# MCB-Wise-1530-v2_0_0.net
KiCad netlist of a schematic drawn in EAGLE
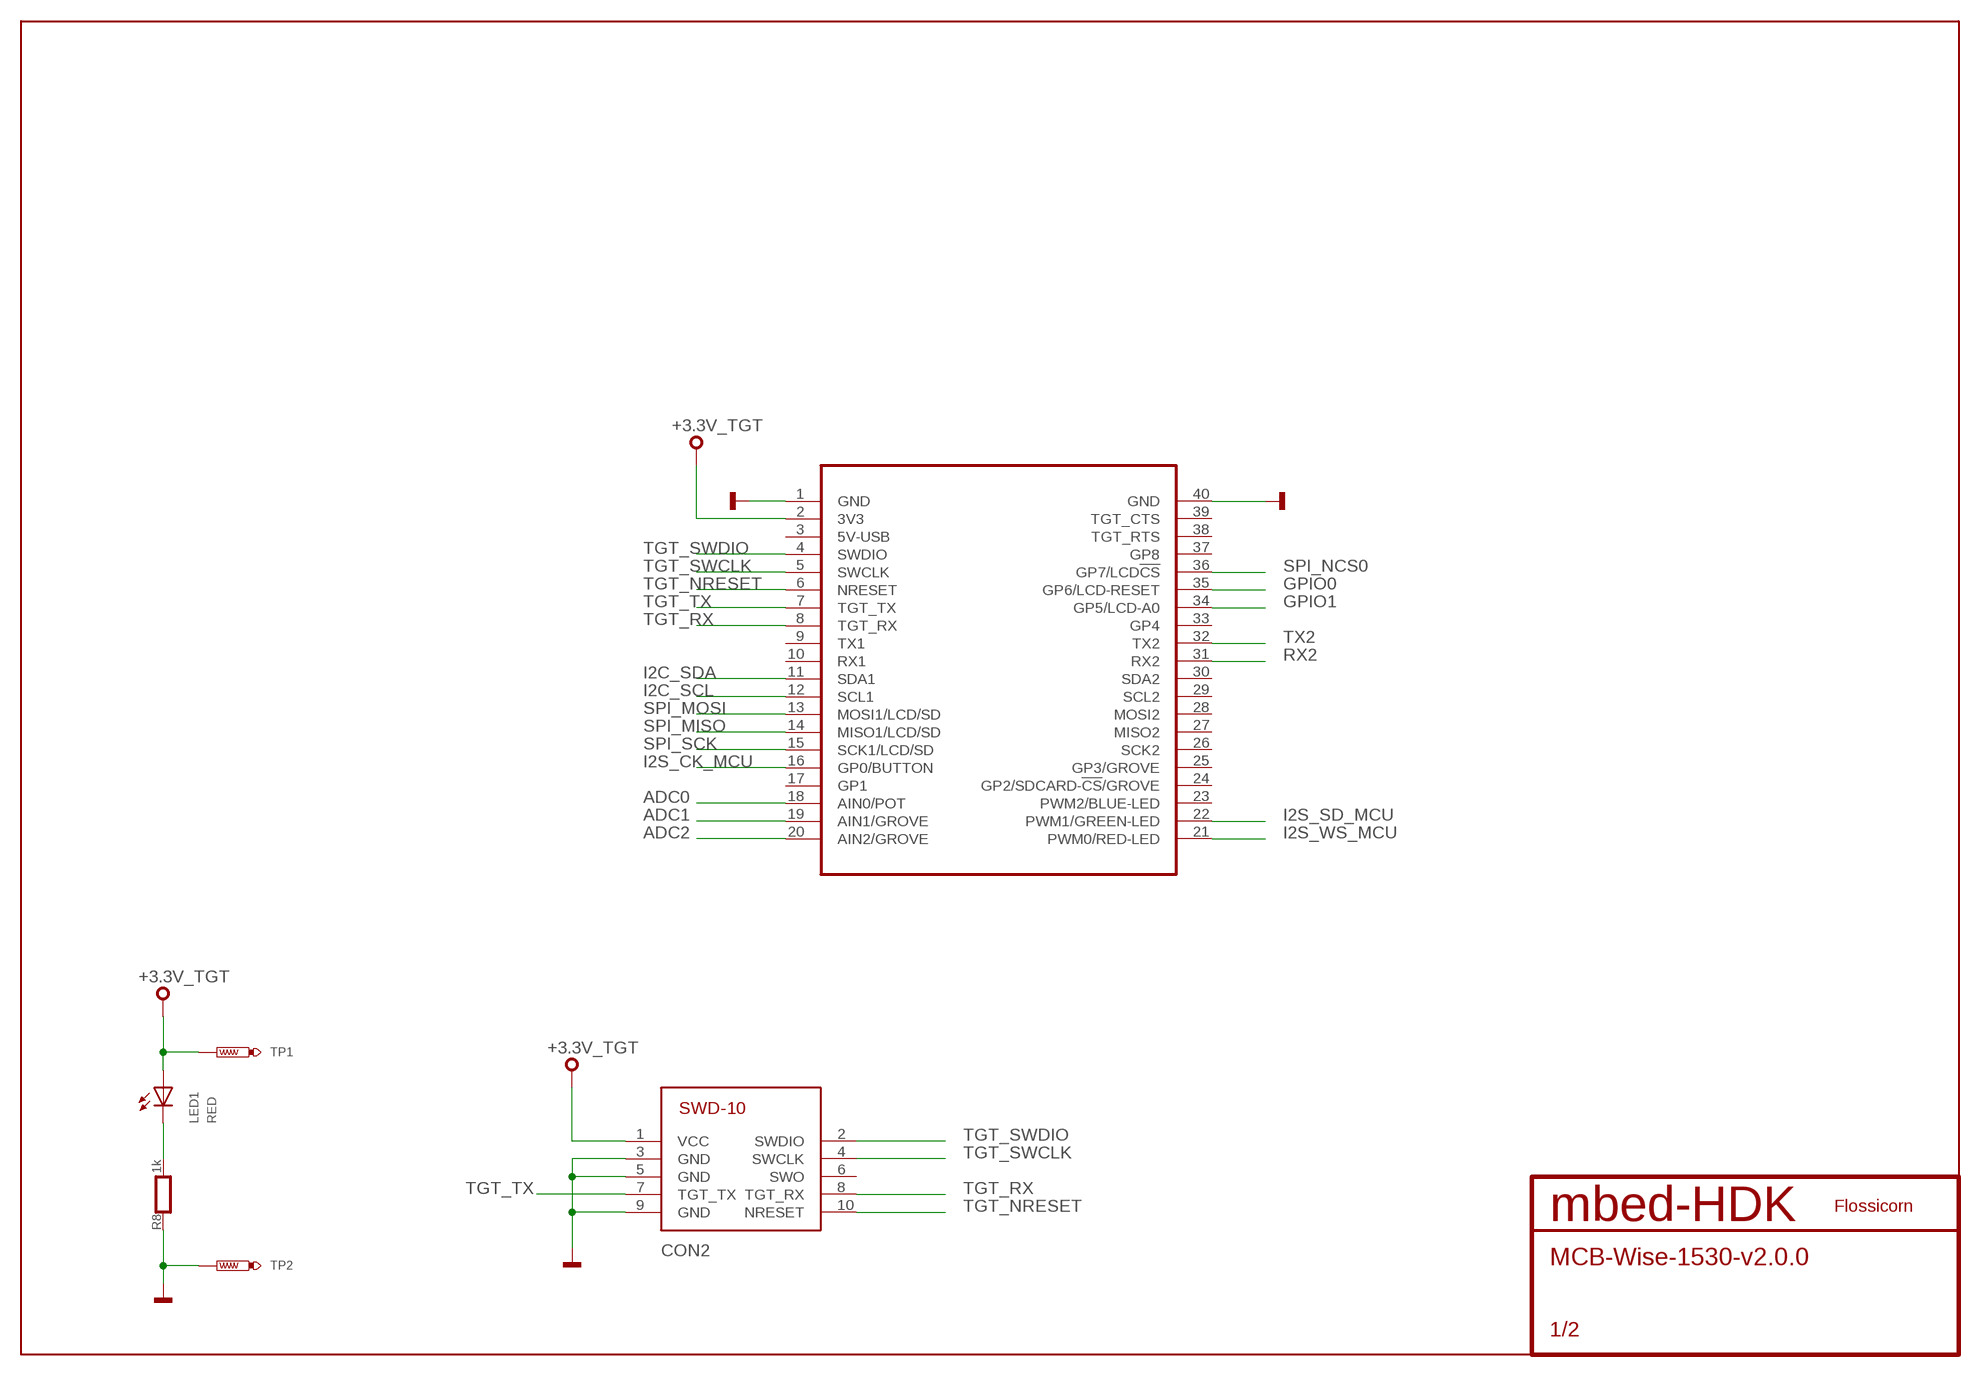
[diagram p0: schematic, sheet 1]
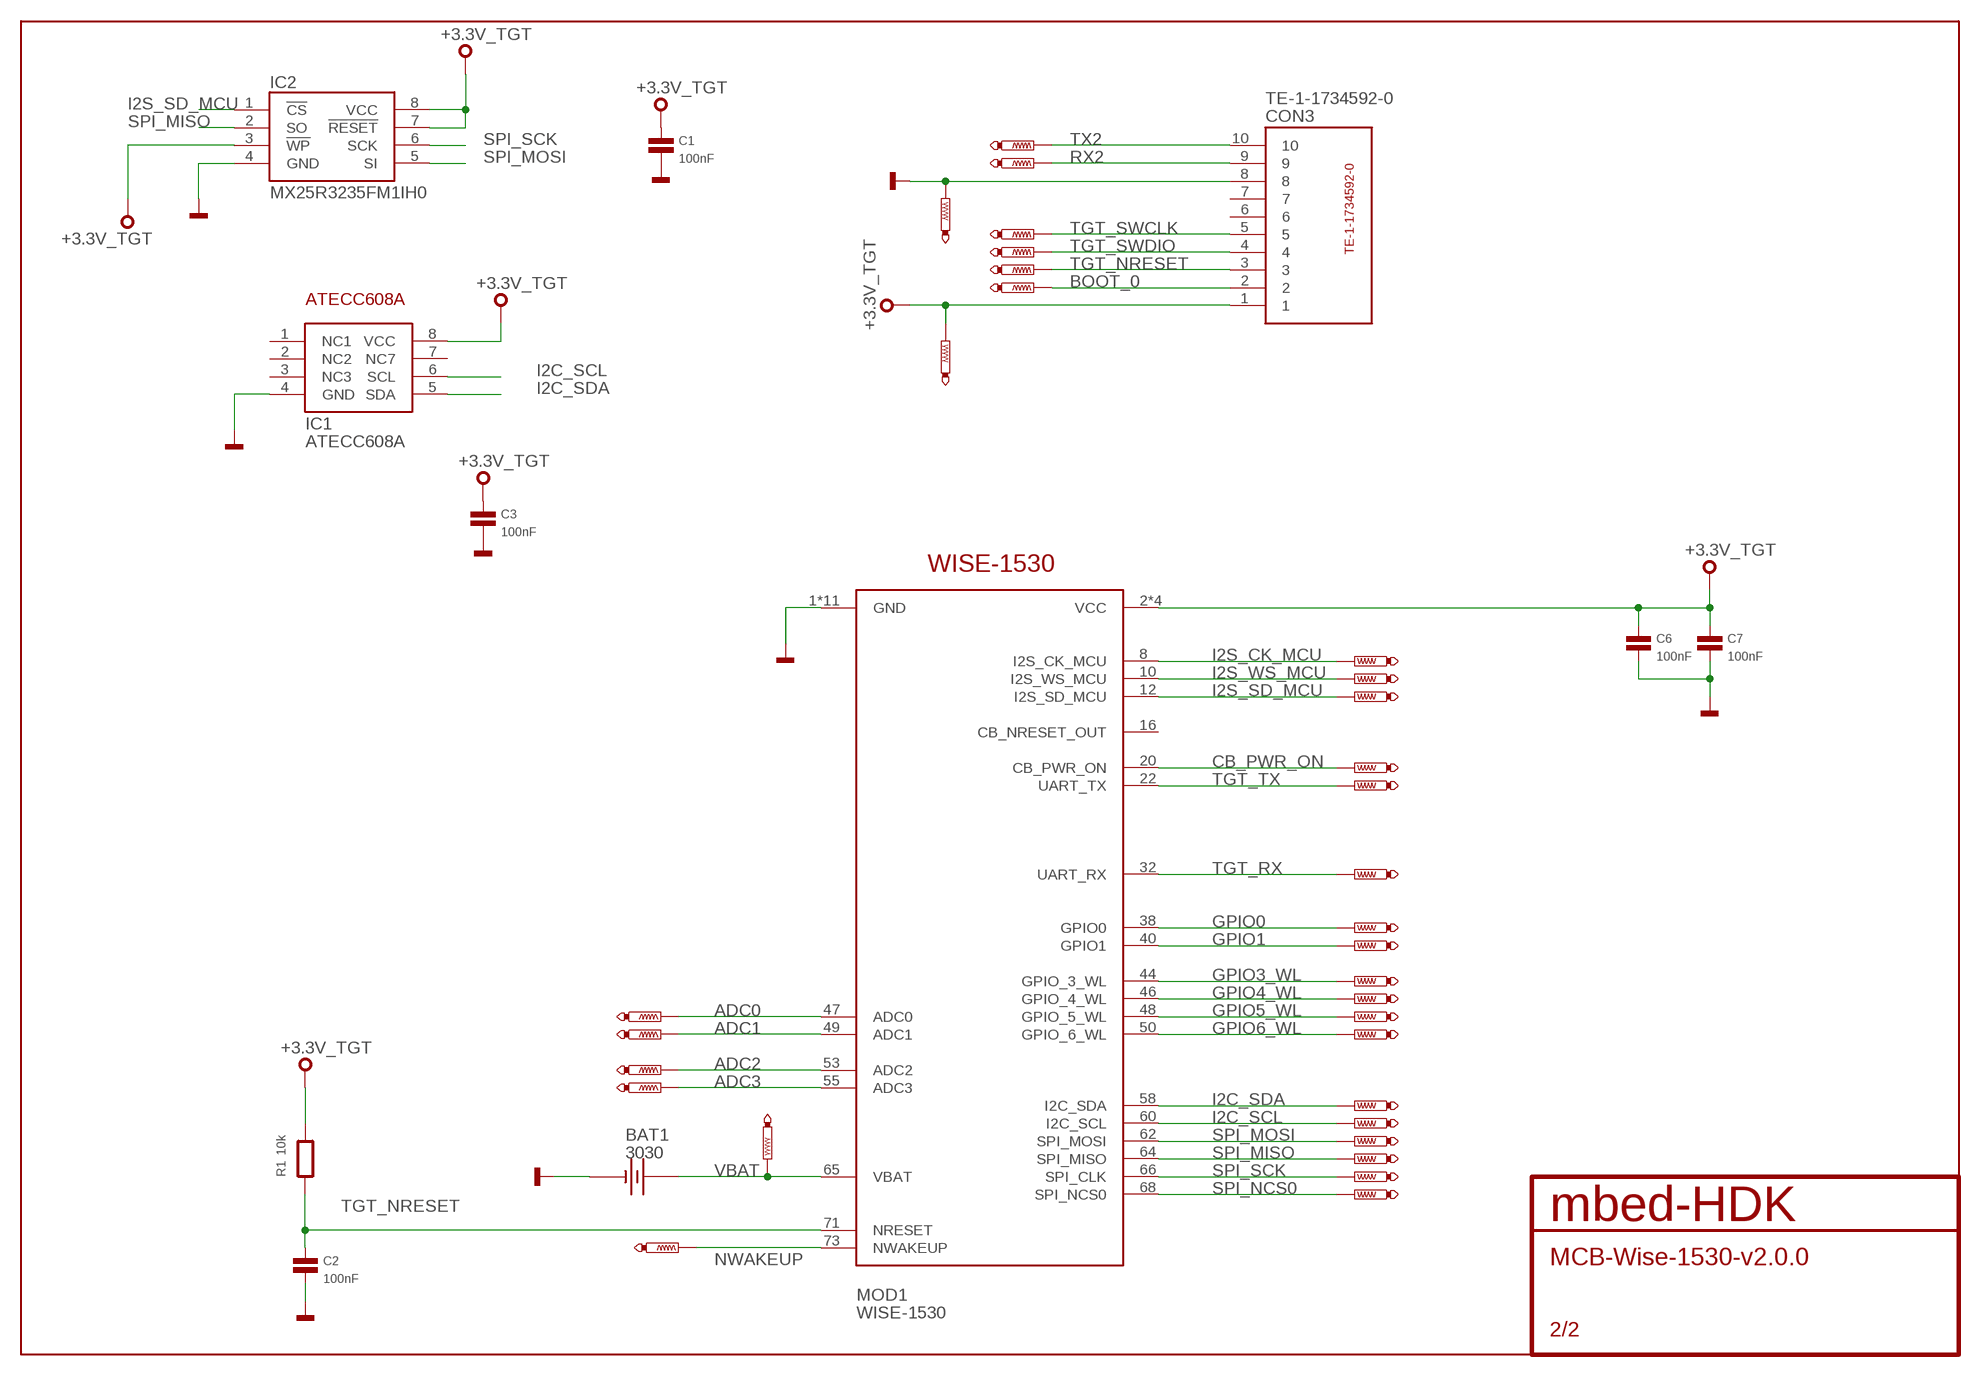
[diagram p1: schematic, sheet 2]

(export (version "E")
  (design (tool "Eeschema 10.0.6"))
  (components
    (comp (ref "CON2")
      (value "SWD-10/TC2050_SMD")
      (footprint "eagle-import:FTSH-105-02")
      (libsource (lib "eagle-import") (part "SWD-10/TC2050_SMD"))
    )
    (comp (ref "LED1")
      (value "RED")
      (footprint "eagle-import:CHIPLED_0603")
      (fields (field (name "MF") "Wurth Electronics Inc"))
      (libsource (lib "eagle-import") (part "SMD_LED0603"))
    )
    (comp (ref "MOD2")
      (value "MODULE_DAUGHTER")
      (footprint "eagle-import:MODULE_DAUGHTER")
      (libsource (lib "eagle-import") (part "MODULE_DAUGHTER"))
    )
    (comp (ref "R8")
      (value "1k")
      (footprint "eagle-import:0603")
      (libsource (lib "eagle-import") (part "RESISTOR0603"))
    )
    (comp (ref "SS1")
      (value "FLOSSICORN0.25")
      (footprint "eagle-import:FLOSSICORN-0.25")
      (libsource (lib "eagle-import") (part "FLOSSICORN0.25"))
    )
    (comp (ref "TP1")
      (value "TEST-POINT-50R-PTH")
      (footprint "eagle-import:TP50-PTH")
      (libsource (lib "eagle-import") (part "TEST-POINT-50R-PTH"))
    )
    (comp (ref "TP2")
      (value "TEST-POINT-50R-PTH")
      (footprint "eagle-import:TP50-PTH")
      (libsource (lib "eagle-import") (part "TEST-POINT-50R-PTH"))
    )
    (comp (ref "BAT1")
      (value "3030")
      (footprint "eagle-import:3030")
      (fields (field (name "MF") "Keystone"))
      (libsource (lib "eagle-import") (part "3030"))
    )
    (comp (ref "C1")
      (value "100nF")
      (footprint "eagle-import:0603")
      (libsource (lib "eagle-import") (part "CAPACITOR0603"))
    )
    (comp (ref "C2")
      (value "100nF")
      (footprint "eagle-import:0603")
      (libsource (lib "eagle-import") (part "CAPACITOR0603"))
    )
    (comp (ref "C3")
      (value "100nF")
      (footprint "eagle-import:0603")
      (libsource (lib "eagle-import") (part "CAPACITOR0603"))
    )
    (comp (ref "C6")
      (value "100nF")
      (footprint "eagle-import:0603")
      (libsource (lib "eagle-import") (part "CAPACITOR0603"))
    )
    (comp (ref "C7")
      (value "100nF")
      (footprint "eagle-import:0603")
      (libsource (lib "eagle-import") (part "CAPACITOR0603"))
    )
    (comp (ref "CON3")
      (value "TE-1-1734592-0")
      (footprint "eagle-import:TE-1-1734592-0")
      (libsource (lib "eagle-import") (part "TE-1-1734592-0"))
    )
    (comp (ref "IC1")
      (value "ATECC608A")
      (footprint "eagle-import:SO8")
      (libsource (lib "eagle-import") (part "ATECC608A"))
    )
    (comp (ref "IC2")
      (value "MX25R3235FM1IH0")
      (footprint "eagle-import:SO8")
      (fields (field (name "MF") "Macronix"))
      (libsource (lib "eagle-import") (part "MX25R3235FM1IH0"))
    )
    (comp (ref "MOD1")
      (value "WISE-1530")
      (footprint "eagle-import:MDT420E02001")
      (libsource (lib "eagle-import") (part "WISE-1530"))
    )
    (comp (ref "R1")
      (value "10k")
      (footprint "eagle-import:0603")
      (libsource (lib "eagle-import") (part "RESISTOR0603"))
    )
    (comp (ref "TP3")
      (value "PTR1TP08R")
      (footprint "eagle-import:TP08R")
      (libsource (lib "eagle-import") (part "PTR1TP08R"))
    )
    (comp (ref "TP4")
      (value "PTR1TP08R")
      (footprint "eagle-import:TP08R")
      (libsource (lib "eagle-import") (part "PTR1TP08R"))
    )
    (comp (ref "TP5")
      (value "PTR1TP08R")
      (footprint "eagle-import:TP08R")
      (libsource (lib "eagle-import") (part "PTR1TP08R"))
    )
    (comp (ref "TP6")
      (value "PTR1TP08R")
      (footprint "eagle-import:TP08R")
      (libsource (lib "eagle-import") (part "PTR1TP08R"))
    )
    (comp (ref "TP7")
      (value "PTR1TP08R")
      (footprint "eagle-import:TP08R")
      (libsource (lib "eagle-import") (part "PTR1TP08R"))
    )
    (comp (ref "TP8")
      (value "PTR1TP08R")
      (footprint "eagle-import:TP08R")
      (libsource (lib "eagle-import") (part "PTR1TP08R"))
    )
    (comp (ref "TP9")
      (value "PTR1TP07R")
      (footprint "eagle-import:TP07R")
      (libsource (lib "eagle-import") (part "PTR1TP07R"))
    )
    (comp (ref "TP10")
      (value "PTR1TP07R")
      (footprint "eagle-import:TP07R")
      (libsource (lib "eagle-import") (part "PTR1TP07R"))
    )
    (comp (ref "TP11")
      (value "PTR1TP07R")
      (footprint "eagle-import:TP07R")
      (libsource (lib "eagle-import") (part "PTR1TP07R"))
    )
    (comp (ref "TP12")
      (value "PTR1TP08R")
      (footprint "eagle-import:TP08R")
      (libsource (lib "eagle-import") (part "PTR1TP08R"))
    )
    (comp (ref "TP13")
      (value "PTR1TP08R")
      (footprint "eagle-import:TP08R")
      (libsource (lib "eagle-import") (part "PTR1TP08R"))
    )
    (comp (ref "TP14")
      (value "PTR1TP07R")
      (footprint "eagle-import:TP07R")
      (libsource (lib "eagle-import") (part "PTR1TP07R"))
    )
    (comp (ref "TP15")
      (value "PTR1TP07R")
      (footprint "eagle-import:TP07R")
      (libsource (lib "eagle-import") (part "PTR1TP07R"))
    )
    (comp (ref "TP16")
      (value "PTR1TP07R")
      (footprint "eagle-import:TP07R")
      (libsource (lib "eagle-import") (part "PTR1TP07R"))
    )
    (comp (ref "TP17")
      (value "PTR1TP07R")
      (footprint "eagle-import:TP07R")
      (libsource (lib "eagle-import") (part "PTR1TP07R"))
    )
    (comp (ref "TP18")
      (value "PTR1TP07R")
      (footprint "eagle-import:TP07R")
      (libsource (lib "eagle-import") (part "PTR1TP07R"))
    )
    (comp (ref "TP19")
      (value "PTR1TP07R")
      (footprint "eagle-import:TP07R")
      (libsource (lib "eagle-import") (part "PTR1TP07R"))
    )
    (comp (ref "TP20")
      (value "PTR1TP07R")
      (footprint "eagle-import:TP07R")
      (libsource (lib "eagle-import") (part "PTR1TP07R"))
    )
    (comp (ref "TP21")
      (value "PTR1TP07R")
      (footprint "eagle-import:TP07R")
      (libsource (lib "eagle-import") (part "PTR1TP07R"))
    )
    (comp (ref "TP22")
      (value "PTR1TP07R")
      (footprint "eagle-import:TP07R")
      (libsource (lib "eagle-import") (part "PTR1TP07R"))
    )
    (comp (ref "TP23")
      (value "PTR1TP07R")
      (footprint "eagle-import:TP07R")
      (libsource (lib "eagle-import") (part "PTR1TP07R"))
    )
    (comp (ref "TP24")
      (value "PTR1TP07R")
      (footprint "eagle-import:TP07R")
      (libsource (lib "eagle-import") (part "PTR1TP07R"))
    )
    (comp (ref "TP25")
      (value "PTR1TP07R")
      (footprint "eagle-import:TP07R")
      (libsource (lib "eagle-import") (part "PTR1TP07R"))
    )
    (comp (ref "TP26")
      (value "PTR1TP07R")
      (footprint "eagle-import:TP07R")
      (libsource (lib "eagle-import") (part "PTR1TP07R"))
    )
    (comp (ref "TP27")
      (value "PTR1TP07R")
      (footprint "eagle-import:TP07R")
      (libsource (lib "eagle-import") (part "PTR1TP07R"))
    )
    (comp (ref "TP28")
      (value "PTR1TP07R")
      (footprint "eagle-import:TP07R")
      (libsource (lib "eagle-import") (part "PTR1TP07R"))
    )
    (comp (ref "TP29")
      (value "PTR1TP07R")
      (footprint "eagle-import:TP07R")
      (libsource (lib "eagle-import") (part "PTR1TP07R"))
    )
    (comp (ref "TP30")
      (value "PTR1TP07R")
      (footprint "eagle-import:TP07R")
      (libsource (lib "eagle-import") (part "PTR1TP07R"))
    )
    (comp (ref "TP31")
      (value "PTR1TP07R")
      (footprint "eagle-import:TP07R")
      (libsource (lib "eagle-import") (part "PTR1TP07R"))
    )
    (comp (ref "TP32")
      (value "PTR1TP07R")
      (footprint "eagle-import:TP07R")
      (libsource (lib "eagle-import") (part "PTR1TP07R"))
    )
    (comp (ref "TP33")
      (value "PTR1TP07R")
      (footprint "eagle-import:TP07R")
      (libsource (lib "eagle-import") (part "PTR1TP07R"))
    )
    (comp (ref "TP34")
      (value "PTR1TP07R")
      (footprint "eagle-import:TP07R")
      (libsource (lib "eagle-import") (part "PTR1TP07R"))
    )
  )
  (nets
    (net (code "1") (name "+3.3V_TGT") (class "Default")
      (node (ref "C1") (pin "1") (pinfunction "P$1_1") (pintype "passive"))
      (node (ref "C3") (pin "1") (pinfunction "P$1_1") (pintype "passive"))
      (node (ref "C6") (pin "1") (pinfunction "P$1_1") (pintype "passive"))
      (node (ref "C7") (pin "1") (pinfunction "P$1_1") (pintype "passive"))
      (node (ref "CON2") (pin "1") (pinfunction "VCC_1") (pintype "bidirectional"))
      (node (ref "CON3") (pin "1") (pinfunction "1_1") (pintype "bidirectional"))
      (node (ref "IC1") (pin "8") (pinfunction "VCC_8") (pintype "bidirectional"))
      (node (ref "IC2") (pin "3") (pinfunction "~{WP}_3") (pintype "bidirectional"))
      (node (ref "IC2") (pin "7") (pinfunction "~{RESET}_7") (pintype "bidirectional"))
      (node (ref "IC2") (pin "8") (pinfunction "VCC_8") (pintype "bidirectional"))
      (node (ref "LED1") (pin "A") (pinfunction "A_A") (pintype "passive"))
      (node (ref "MOD1") (pin "2") (pinfunction "VCC_2") (pintype "bidirectional"))
      (node (ref "MOD1") (pin "4") (pinfunction "VCC_4") (pintype "bidirectional"))
      (node (ref "MOD1") (pin "72") (pinfunction "VCC_72") (pintype "bidirectional"))
      (node (ref "MOD1") (pin "74") (pinfunction "VCC_74") (pintype "bidirectional"))
      (node (ref "MOD2") (pin "2") (pinfunction "3V3_2") (pintype "bidirectional"))
      (node (ref "R1") (pin "2") (pinfunction "P$2_2") (pintype "passive"))
      (node (ref "TP1") (pin "TP") (pinfunction "TP_TP") (pintype "input"))
      (node (ref "TP12") (pin "TP") (pinfunction "TP_TP") (pintype "input"))
    )
    (net (code "2") (name "ADC0") (class "Default")
      (node (ref "MOD1") (pin "47") (pinfunction "ADC0_47") (pintype "bidirectional"))
      (node (ref "MOD2") (pin "18") (pinfunction "AIN0/POT_18") (pintype "bidirectional"))
      (node (ref "TP29") (pin "TP") (pinfunction "TP_TP") (pintype "input"))
    )
    (net (code "3") (name "ADC1") (class "Default")
      (node (ref "MOD1") (pin "49") (pinfunction "ADC1_49") (pintype "bidirectional"))
      (node (ref "MOD2") (pin "19") (pinfunction "AIN1/GROVE_19") (pintype "bidirectional"))
      (node (ref "TP30") (pin "TP") (pinfunction "TP_TP") (pintype "input"))
    )
    (net (code "4") (name "ADC2") (class "Default")
      (node (ref "MOD1") (pin "53") (pinfunction "ADC2_53") (pintype "bidirectional"))
      (node (ref "MOD2") (pin "20") (pinfunction "AIN2/GROVE_20") (pintype "bidirectional"))
      (node (ref "TP31") (pin "TP") (pinfunction "TP_TP") (pintype "input"))
    )
    (net (code "5") (name "ADC3") (class "Default")
      (node (ref "MOD1") (pin "55") (pinfunction "ADC3_55") (pintype "bidirectional"))
      (node (ref "TP32") (pin "TP") (pinfunction "TP_TP") (pintype "input"))
    )
    (net (code "6") (name "BOOT_0") (class "Default")
      (node (ref "CON3") (pin "2") (pinfunction "2_2") (pintype "bidirectional"))
      (node (ref "TP8") (pin "TP") (pinfunction "TP_TP") (pintype "input"))
    )
    (net (code "7") (name "CB_PWR_ON") (class "Default")
      (node (ref "MOD1") (pin "20") (pinfunction "CB_PWR_ON_20") (pintype "bidirectional"))
      (node (ref "TP14") (pin "TP") (pinfunction "TP_TP") (pintype "input"))
    )
    (net (code "8") (name "GND") (class "Default")
      (node (ref "BAT1") (pin "-") (pinfunction "-_-") (pintype "bidirectional"))
      (node (ref "C1") (pin "2") (pinfunction "P$2_2") (pintype "passive"))
      (node (ref "C2") (pin "2") (pinfunction "P$2_2") (pintype "passive"))
      (node (ref "C3") (pin "2") (pinfunction "P$2_2") (pintype "passive"))
      (node (ref "C6") (pin "2") (pinfunction "P$2_2") (pintype "passive"))
      (node (ref "C7") (pin "2") (pinfunction "P$2_2") (pintype "passive"))
      (node (ref "CON2") (pin "3") (pinfunction "GND_3") (pintype "bidirectional"))
      (node (ref "CON2") (pin "5") (pinfunction "GND_5") (pintype "bidirectional"))
      (node (ref "CON2") (pin "9") (pinfunction "GND_9") (pintype "bidirectional"))
      (node (ref "CON3") (pin "8") (pinfunction "8_8") (pintype "bidirectional"))
      (node (ref "IC1") (pin "4") (pinfunction "GND_4") (pintype "bidirectional"))
      (node (ref "IC2") (pin "4") (pinfunction "GND_4") (pintype "bidirectional"))
      (node (ref "MOD1") (pin "1") (pinfunction "GND_1") (pintype "bidirectional"))
      (node (ref "MOD1") (pin "18") (pinfunction "GND_18") (pintype "bidirectional"))
      (node (ref "MOD1") (pin "33") (pinfunction "GND_33") (pintype "bidirectional"))
      (node (ref "MOD1") (pin "39") (pinfunction "GND_39") (pintype "bidirectional"))
      (node (ref "MOD1") (pin "45") (pinfunction "GND_45") (pintype "bidirectional"))
      (node (ref "MOD1") (pin "51") (pinfunction "GND_51") (pintype "bidirectional"))
      (node (ref "MOD1") (pin "57") (pinfunction "GND_57") (pintype "bidirectional"))
      (node (ref "MOD1") (pin "63") (pinfunction "GND_63") (pintype "bidirectional"))
      (node (ref "MOD1") (pin "69") (pinfunction "GND_69") (pintype "bidirectional"))
      (node (ref "MOD1") (pin "7") (pinfunction "GND_7") (pintype "bidirectional"))
      (node (ref "MOD1") (pin "75") (pinfunction "GND_75") (pintype "bidirectional"))
      (node (ref "MOD2") (pin "1") (pinfunction "GND_1") (pintype "bidirectional"))
      (node (ref "MOD2") (pin "40") (pinfunction "GND_40") (pintype "bidirectional"))
      (node (ref "R8") (pin "1") (pinfunction "P$1_1") (pintype "passive"))
      (node (ref "TP13") (pin "TP") (pinfunction "TP_TP") (pintype "input"))
      (node (ref "TP2") (pin "TP") (pinfunction "TP_TP") (pintype "input"))
    )
    (net (code "9") (name "GPIO0") (class "Default")
      (node (ref "MOD1") (pin "38") (pinfunction "GPIO0_38") (pintype "bidirectional"))
      (node (ref "MOD2") (pin "35") (pinfunction "GP6/LCD-RESET_35") (pintype "bidirectional"))
      (node (ref "TP27") (pin "TP") (pinfunction "TP_TP") (pintype "input"))
    )
    (net (code "10") (name "GPIO1") (class "Default")
      (node (ref "MOD1") (pin "40") (pinfunction "GPIO1_40") (pintype "bidirectional"))
      (node (ref "MOD2") (pin "34") (pinfunction "GP5/LCD-A0_34") (pintype "bidirectional"))
      (node (ref "TP26") (pin "TP") (pinfunction "TP_TP") (pintype "input"))
    )
    (net (code "11") (name "GPIO3_WL") (class "Default")
      (node (ref "MOD1") (pin "44") (pinfunction "GPIO_3_WL_44") (pintype "bidirectional"))
      (node (ref "TP25") (pin "TP") (pinfunction "TP_TP") (pintype "input"))
    )
    (net (code "12") (name "GPIO4_WL") (class "Default")
      (node (ref "MOD1") (pin "46") (pinfunction "GPIO_4_WL_46") (pintype "bidirectional"))
      (node (ref "TP24") (pin "TP") (pinfunction "TP_TP") (pintype "input"))
    )
    (net (code "13") (name "GPIO5_WL") (class "Default")
      (node (ref "MOD1") (pin "48") (pinfunction "GPIO_5_WL_48") (pintype "bidirectional"))
      (node (ref "TP23") (pin "TP") (pinfunction "TP_TP") (pintype "input"))
    )
    (net (code "14") (name "GPIO6_WL") (class "Default")
      (node (ref "MOD1") (pin "50") (pinfunction "GPIO_6_WL_50") (pintype "bidirectional"))
      (node (ref "TP22") (pin "TP") (pinfunction "TP_TP") (pintype "input"))
    )
    (net (code "15") (name "I2C_SCL") (class "Default")
      (node (ref "IC1") (pin "6") (pinfunction "SCL_6") (pintype "bidirectional"))
      (node (ref "MOD1") (pin "60") (pinfunction "I2C_SCL_60") (pintype "bidirectional"))
      (node (ref "MOD2") (pin "12") (pinfunction "SCL1_12") (pintype "bidirectional"))
      (node (ref "TP20") (pin "TP") (pinfunction "TP_TP") (pintype "input"))
    )
    (net (code "16") (name "I2C_SDA") (class "Default")
      (node (ref "IC1") (pin "5") (pinfunction "SDA_5") (pintype "bidirectional"))
      (node (ref "MOD1") (pin "58") (pinfunction "I2C_SDA_58") (pintype "bidirectional"))
      (node (ref "MOD2") (pin "11") (pinfunction "SDA1_11") (pintype "bidirectional"))
      (node (ref "TP21") (pin "TP") (pinfunction "TP_TP") (pintype "input"))
    )
    (net (code "17") (name "I2S_CK_MCU") (class "Default")
      (node (ref "MOD1") (pin "8") (pinfunction "I2S_CK_MCU_8") (pintype "bidirectional"))
      (node (ref "MOD2") (pin "16") (pinfunction "GP0/BUTTON_16") (pintype "bidirectional"))
      (node (ref "TP9") (pin "TP") (pinfunction "TP_TP") (pintype "input"))
    )
    (net (code "18") (name "I2S_SD_MCU") (class "Default")
      (node (ref "IC2") (pin "1") (pinfunction "~{CS}_1") (pintype "bidirectional"))
      (node (ref "MOD1") (pin "12") (pinfunction "I2S_SD_MCU_12") (pintype "bidirectional"))
      (node (ref "MOD2") (pin "22") (pinfunction "PWM1/GREEN-LED_22") (pintype "bidirectional"))
      (node (ref "TP11") (pin "TP") (pinfunction "TP_TP") (pintype "input"))
    )
    (net (code "19") (name "I2S_WS_MCU") (class "Default")
      (node (ref "MOD1") (pin "10") (pinfunction "I2S_WS_MCU_10") (pintype "bidirectional"))
      (node (ref "MOD2") (pin "21") (pinfunction "PWM0/RED-LED_21") (pintype "bidirectional"))
      (node (ref "TP10") (pin "TP") (pinfunction "TP_TP") (pintype "input"))
    )
    (net (code "20") (name "NWAKEUP") (class "Default")
      (node (ref "MOD1") (pin "73") (pinfunction "NWAKEUP_73") (pintype "bidirectional"))
      (node (ref "TP34") (pin "TP") (pinfunction "TP_TP") (pintype "input"))
    )
    (net (code "21") (name "Net-(R8-P$2)") (class "Default")
      (node (ref "LED1") (pin "C") (pinfunction "C_C") (pintype "passive"))
      (node (ref "R8") (pin "2") (pinfunction "P$2_2") (pintype "passive"))
    )
    (net (code "22") (name "RX2") (class "Default")
      (node (ref "CON3") (pin "9") (pinfunction "9_9") (pintype "bidirectional"))
      (node (ref "MOD2") (pin "31") (pinfunction "RX2_31") (pintype "bidirectional"))
      (node (ref "TP6") (pin "TP") (pinfunction "TP_TP") (pintype "input"))
    )
    (net (code "23") (name "SPI_MISO") (class "Default")
      (node (ref "IC2") (pin "2") (pinfunction "SO_2") (pintype "bidirectional"))
      (node (ref "MOD1") (pin "64") (pinfunction "SPI_MISO_64") (pintype "bidirectional"))
      (node (ref "MOD2") (pin "14") (pinfunction "MISO1/LCD/SD_14") (pintype "bidirectional"))
      (node (ref "TP18") (pin "TP") (pinfunction "TP_TP") (pintype "input"))
    )
    (net (code "24") (name "SPI_MOSI") (class "Default")
      (node (ref "IC2") (pin "5") (pinfunction "SI_5") (pintype "bidirectional"))
      (node (ref "MOD1") (pin "62") (pinfunction "SPI_MOSI_62") (pintype "bidirectional"))
      (node (ref "MOD2") (pin "13") (pinfunction "MOSI1/LCD/SD_13") (pintype "bidirectional"))
      (node (ref "TP19") (pin "TP") (pinfunction "TP_TP") (pintype "input"))
    )
    (net (code "25") (name "SPI_NCS0") (class "Default")
      (node (ref "MOD1") (pin "68") (pinfunction "SPI_NCS0_68") (pintype "bidirectional"))
      (node (ref "MOD2") (pin "36") (pinfunction "GP7/LCD~{CS}_36") (pintype "bidirectional"))
      (node (ref "TP16") (pin "TP") (pinfunction "TP_TP") (pintype "input"))
    )
    (net (code "26") (name "SPI_SCK") (class "Default")
      (node (ref "IC2") (pin "6") (pinfunction "SCK_6") (pintype "bidirectional"))
      (node (ref "MOD1") (pin "66") (pinfunction "SPI_CLK_66") (pintype "bidirectional"))
      (node (ref "MOD2") (pin "15") (pinfunction "SCK1/LCD/SD_15") (pintype "bidirectional"))
      (node (ref "TP17") (pin "TP") (pinfunction "TP_TP") (pintype "input"))
    )
    (net (code "27") (name "TGT_NRESET") (class "Default")
      (node (ref "C2") (pin "1") (pinfunction "P$1_1") (pintype "passive"))
      (node (ref "CON2") (pin "10") (pinfunction "NRESET_10") (pintype "bidirectional"))
      (node (ref "CON3") (pin "3") (pinfunction "3_3") (pintype "bidirectional"))
      (node (ref "MOD1") (pin "71") (pinfunction "NRESET_71") (pintype "bidirectional"))
      (node (ref "MOD2") (pin "6") (pinfunction "NRESET_6") (pintype "bidirectional"))
      (node (ref "R1") (pin "1") (pinfunction "P$1_1") (pintype "passive"))
      (node (ref "TP5") (pin "TP") (pinfunction "TP_TP") (pintype "input"))
    )
    (net (code "28") (name "TGT_RX") (class "Default")
      (node (ref "CON2") (pin "8") (pinfunction "TGT_RX_8") (pintype "bidirectional"))
      (node (ref "MOD1") (pin "32") (pinfunction "UART_RX_32") (pintype "bidirectional"))
      (node (ref "MOD2") (pin "8") (pinfunction "TGT_RX_8") (pintype "bidirectional"))
      (node (ref "TP28") (pin "TP") (pinfunction "TP_TP") (pintype "input"))
    )
    (net (code "29") (name "TGT_SWCLK") (class "Default")
      (node (ref "CON2") (pin "4") (pinfunction "SWCLK_4") (pintype "bidirectional"))
      (node (ref "CON3") (pin "5") (pinfunction "5_5") (pintype "bidirectional"))
      (node (ref "MOD2") (pin "5") (pinfunction "SWCLK_5") (pintype "bidirectional"))
      (node (ref "TP3") (pin "TP") (pinfunction "TP_TP") (pintype "input"))
    )
    (net (code "30") (name "TGT_SWDIO") (class "Default")
      (node (ref "CON2") (pin "2") (pinfunction "SWDIO_2") (pintype "bidirectional"))
      (node (ref "CON3") (pin "4") (pinfunction "4_4") (pintype "bidirectional"))
      (node (ref "MOD2") (pin "4") (pinfunction "SWDIO_4") (pintype "bidirectional"))
      (node (ref "TP4") (pin "TP") (pinfunction "TP_TP") (pintype "input"))
    )
    (net (code "31") (name "TGT_TX") (class "Default")
      (node (ref "CON2") (pin "7") (pinfunction "TGT_TX_7") (pintype "bidirectional"))
      (node (ref "MOD1") (pin "22") (pinfunction "UART_TX_22") (pintype "bidirectional"))
      (node (ref "MOD2") (pin "7") (pinfunction "TGT_TX_7") (pintype "bidirectional"))
      (node (ref "TP15") (pin "TP") (pinfunction "TP_TP") (pintype "input"))
    )
    (net (code "32") (name "TX2") (class "Default")
      (node (ref "CON3") (pin "10") (pinfunction "10_10") (pintype "bidirectional"))
      (node (ref "MOD2") (pin "32") (pinfunction "TX2_32") (pintype "bidirectional"))
      (node (ref "TP7") (pin "TP") (pinfunction "TP_TP") (pintype "input"))
    )
    (net (code "33") (name "VBAT") (class "Default")
      (node (ref "BAT1") (pin "+1") (pinfunction "+_+1") (pintype "bidirectional"))
      (node (ref "BAT1") (pin "+2") (pinfunction "+_+2") (pintype "bidirectional"))
      (node (ref "MOD1") (pin "65") (pinfunction "VBAT_65") (pintype "bidirectional"))
      (node (ref "TP33") (pin "TP") (pinfunction "TP_TP") (pintype "input"))
    )
    (net (code "34") (name "unconnected-(CON2-SWO-Pad6)") (class "Default")
      (node (ref "CON2") (pin "6") (pinfunction "SWO_6") (pintype "bidirectional"))
    )
    (net (code "35") (name "unconnected-(CON3-Pad6)") (class "Default")
      (node (ref "CON3") (pin "6") (pinfunction "6_6") (pintype "bidirectional"))
    )
    (net (code "36") (name "unconnected-(CON3-Pad7)") (class "Default")
      (node (ref "CON3") (pin "7") (pinfunction "7_7") (pintype "bidirectional"))
    )
    (net (code "37") (name "unconnected-(IC1-NC1-Pad1)") (class "Default")
      (node (ref "IC1") (pin "1") (pinfunction "NC1_1") (pintype "bidirectional"))
    )
    (net (code "38") (name "unconnected-(IC1-NC2-Pad2)") (class "Default")
      (node (ref "IC1") (pin "2") (pinfunction "NC2_2") (pintype "bidirectional"))
    )
    (net (code "39") (name "unconnected-(IC1-NC3-Pad3)") (class "Default")
      (node (ref "IC1") (pin "3") (pinfunction "NC3_3") (pintype "bidirectional"))
    )
    (net (code "40") (name "unconnected-(IC1-NC7-Pad7)") (class "Default")
      (node (ref "IC1") (pin "7") (pinfunction "NC7_7") (pintype "bidirectional"))
    )
    (net (code "41") (name "unconnected-(MOD1-CB_NRESET_OUT-Pad16)") (class "Default")
      (node (ref "MOD1") (pin "16") (pinfunction "CB_NRESET_OUT_16") (pintype "bidirectional"))
    )
    (net (code "42") (name "unconnected-(MOD2-5V-USB-Pad3)") (class "Default")
      (node (ref "MOD2") (pin "3") (pinfunction "5V-USB_3") (pintype "bidirectional"))
    )
    (net (code "43") (name "unconnected-(MOD2-GP1-Pad17)") (class "Default")
      (node (ref "MOD2") (pin "17") (pinfunction "GP1_17") (pintype "bidirectional"))
    )
    (net (code "44") (name "unconnected-(MOD2-GP2{slash}SDCARD-~{CS}{slash}GROVE-Pad24)") (class "Default")
      (node (ref "MOD2") (pin "24") (pinfunction "GP2/SDCARD-~{CS}/GROVE_24") (pintype "bidirectional"))
    )
    (net (code "45") (name "unconnected-(MOD2-GP3{slash}GROVE-Pad25)") (class "Default")
      (node (ref "MOD2") (pin "25") (pinfunction "GP3/GROVE_25") (pintype "bidirectional"))
    )
    (net (code "46") (name "unconnected-(MOD2-GP4-Pad33)") (class "Default")
      (node (ref "MOD2") (pin "33") (pinfunction "GP4_33") (pintype "bidirectional"))
    )
    (net (code "47") (name "unconnected-(MOD2-GP8-Pad37)") (class "Default")
      (node (ref "MOD2") (pin "37") (pinfunction "GP8_37") (pintype "bidirectional"))
    )
    (net (code "48") (name "unconnected-(MOD2-MISO2-Pad27)") (class "Default")
      (node (ref "MOD2") (pin "27") (pinfunction "MISO2_27") (pintype "bidirectional"))
    )
    (net (code "49") (name "unconnected-(MOD2-MOSI2-Pad28)") (class "Default")
      (node (ref "MOD2") (pin "28") (pinfunction "MOSI2_28") (pintype "bidirectional"))
    )
    (net (code "50") (name "unconnected-(MOD2-PWM2{slash}BLUE-LED-Pad23)") (class "Default")
      (node (ref "MOD2") (pin "23") (pinfunction "PWM2/BLUE-LED_23") (pintype "bidirectional"))
    )
    (net (code "51") (name "unconnected-(MOD2-RX1-Pad10)") (class "Default")
      (node (ref "MOD2") (pin "10") (pinfunction "RX1_10") (pintype "bidirectional"))
    )
    (net (code "52") (name "unconnected-(MOD2-SCK2-Pad26)") (class "Default")
      (node (ref "MOD2") (pin "26") (pinfunction "SCK2_26") (pintype "bidirectional"))
    )
    (net (code "53") (name "unconnected-(MOD2-SCL2-Pad29)") (class "Default")
      (node (ref "MOD2") (pin "29") (pinfunction "SCL2_29") (pintype "bidirectional"))
    )
    (net (code "54") (name "unconnected-(MOD2-SDA2-Pad30)") (class "Default")
      (node (ref "MOD2") (pin "30") (pinfunction "SDA2_30") (pintype "bidirectional"))
    )
    (net (code "55") (name "unconnected-(MOD2-TGT_CTS-Pad39)") (class "Default")
      (node (ref "MOD2") (pin "39") (pinfunction "TGT_CTS_39") (pintype "bidirectional"))
    )
    (net (code "56") (name "unconnected-(MOD2-TGT_RTS-Pad38)") (class "Default")
      (node (ref "MOD2") (pin "38") (pinfunction "TGT_RTS_38") (pintype "bidirectional"))
    )
    (net (code "57") (name "unconnected-(MOD2-TX1-Pad9)") (class "Default")
      (node (ref "MOD2") (pin "9") (pinfunction "TX1_9") (pintype "bidirectional"))
    )
  )
)
